# ADXL372_circuit.net
KiCad netlist of a schematic drawn in EAGLE
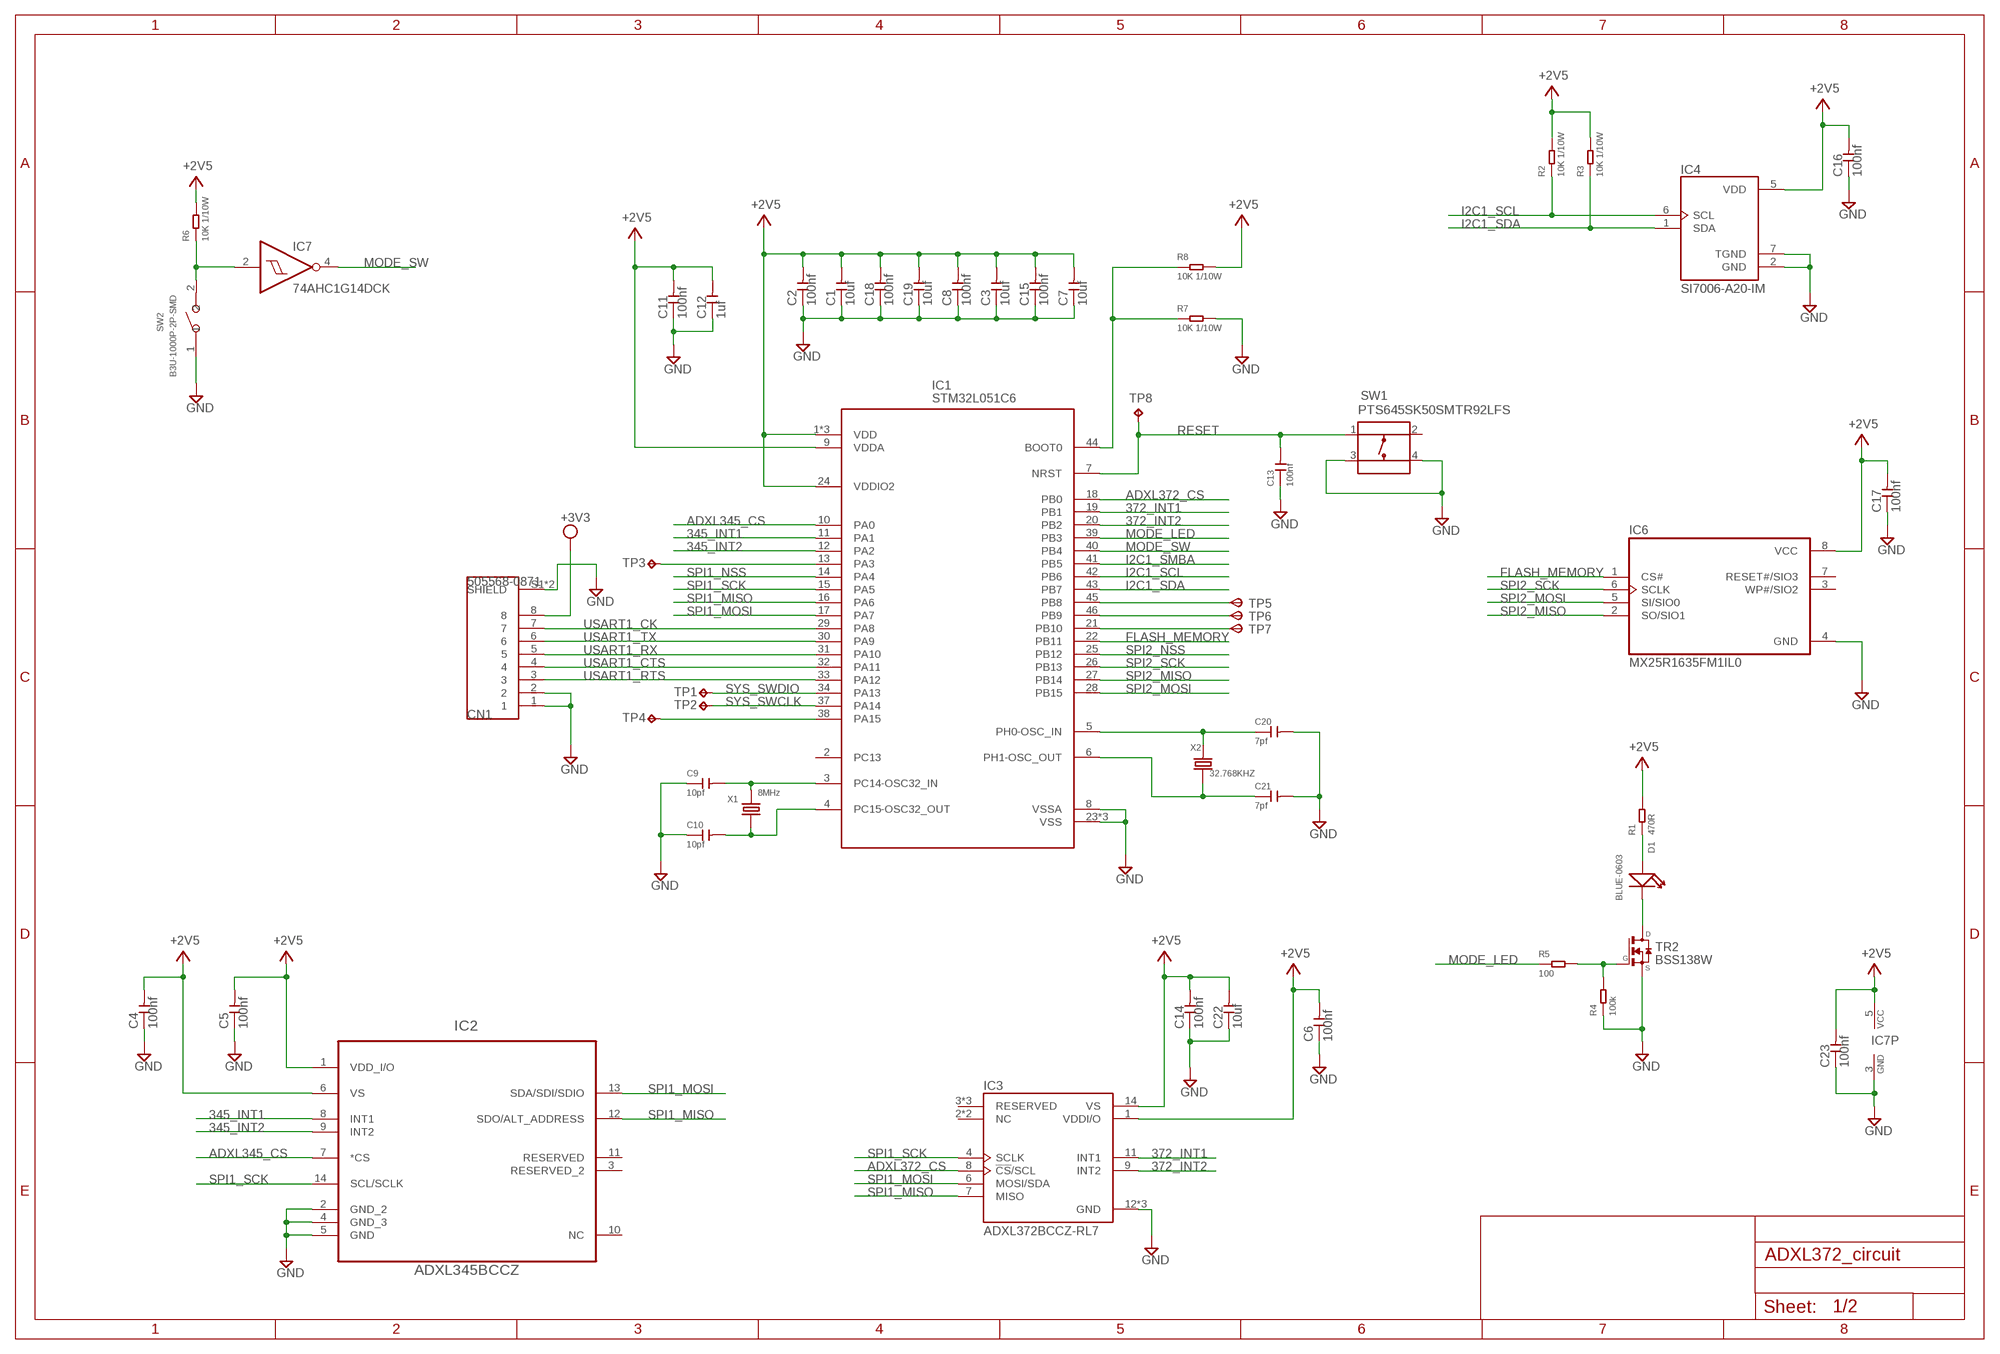
[diagram p0: schematic, sheet 1]
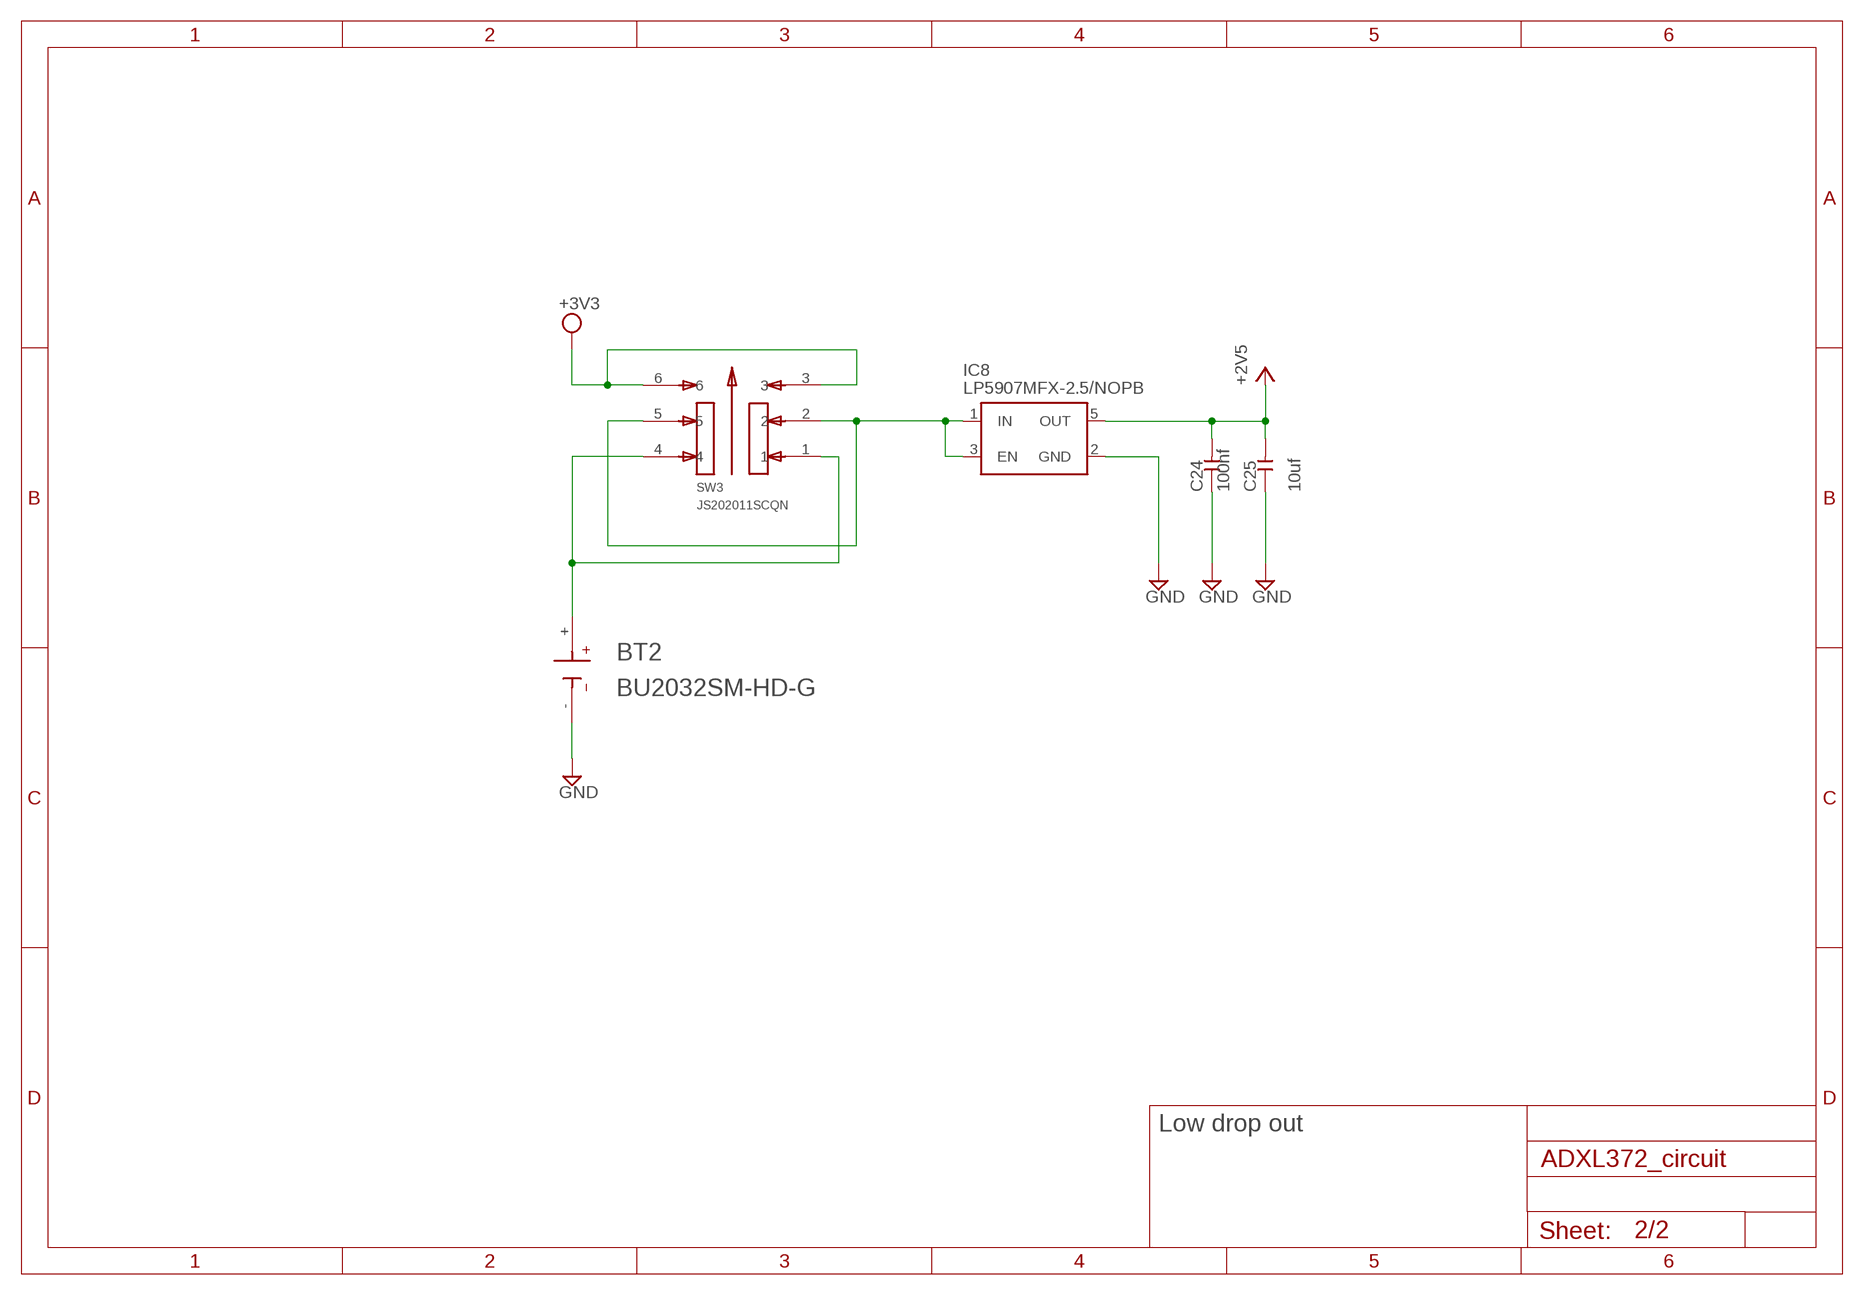
[diagram p1: schematic, sheet 2]

(export (version "E")
  (design (tool "Eeschema 10.0.6"))
  (components
    (comp (ref "BT2")
      (value "BU2032SM-HD-G")
      (footprint "eagle-import:BAT_BU2032SM-HD-G")
      (fields (field (name "DIGI-KEY_PART_NUMBER") "BU2032SM-HD-GCT-ND") (field (name "MF") "MPD _Memory"))
      (libsource (lib "eagle-import") (part "BU2032SM-HD-G"))
    )
    (comp (ref "C24")
      (value "100nf")
      (footprint "eagle-import:C0603")
      (fields (field (name "MPN") "CC0603KRX7R9BB104"))
      (libsource (lib "eagle-import") (part "CERAMIC-100NF-50V-10%-X7R(0603)"))
    )
    (comp (ref "C25")
      (value "10uf")
      (footprint "eagle-import:C0805")
      (fields (field (name "MPN") "CC0805ZKY5V6BB106"))
      (libsource (lib "eagle-import") (part "CERAMIC-10UF-10V-(-20%～+80%)-Y5V(0805)"))
    )
    (comp (ref "IC8")
      (value "LP5907MFX-2.5/NOPB")
      (footprint "eagle-import:SOT95P280X145-5N")
      (fields (field (name "DIGI-KEY_PART_NUMBER") "296-40356-1-ND") (field (name "MF") "Texas Instruments"))
      (libsource (lib "eagle-import") (part "LP5907MFX-2.5/NOPB"))
    )
    (comp (ref "SW3")
      (value "JS202011SCQN")
      (footprint "eagle-import:SW_JS202011SCQN")
      (fields (field (name "DIGI-KEY_PART_NUMBER") "401-2002-1-ND") (field (name "MF") "C&K"))
      (libsource (lib "eagle-import") (part "JS202011SCQN"))
    )
    (comp (ref "C1")
      (value "10uf")
      (footprint "eagle-import:C0805")
      (fields (field (name "MPN") "CC0805ZKY5V6BB106"))
      (libsource (lib "eagle-import") (part "CERAMIC-10UF-10V-(-20%～+80%)-Y5V(0805)"))
    )
    (comp (ref "C2")
      (value "100nf")
      (footprint "eagle-import:C0603")
      (fields (field (name "MPN") "CC0603KRX7R9BB104"))
      (libsource (lib "eagle-import") (part "CERAMIC-100NF-50V-10%-X7R(0603)"))
    )
    (comp (ref "C3")
      (value "10uf")
      (footprint "eagle-import:C0805")
      (fields (field (name "MPN") "CC0805ZKY5V6BB106"))
      (libsource (lib "eagle-import") (part "CERAMIC-10UF-10V-(-20%～+80%)-Y5V(0805)"))
    )
    (comp (ref "C4")
      (value "100nf")
      (footprint "eagle-import:C0603")
      (fields (field (name "MPN") "CC0603KRX7R9BB104"))
      (libsource (lib "eagle-import") (part "CERAMIC-100NF-50V-10%-X7R(0603)"))
    )
    (comp (ref "C5")
      (value "100nf")
      (footprint "eagle-import:C0603")
      (fields (field (name "MPN") "CC0603KRX7R9BB104"))
      (libsource (lib "eagle-import") (part "CERAMIC-100NF-50V-10%-X7R(0603)"))
    )
    (comp (ref "C6")
      (value "100nf")
      (footprint "eagle-import:C0603")
      (fields (field (name "MPN") "CC0603KRX7R9BB104"))
      (libsource (lib "eagle-import") (part "CERAMIC-100NF-50V-10%-X7R(0603)"))
    )
    (comp (ref "C7")
      (value "10uf")
      (footprint "eagle-import:C0805")
      (fields (field (name "MPN") "CC0805ZKY5V6BB106"))
      (libsource (lib "eagle-import") (part "CERAMIC-10UF-10V-(-20%～+80%)-Y5V(0805)"))
    )
    (comp (ref "C8")
      (value "100nf")
      (footprint "eagle-import:C0603")
      (fields (field (name "MPN") "CC0603KRX7R9BB104"))
      (libsource (lib "eagle-import") (part "CERAMIC-100NF-50V-10%-X7R(0603)"))
    )
    (comp (ref "C9")
      (value "10pf")
      (footprint "eagle-import:C0603")
      (fields (field (name "MPN") "CC0603JRNPO9BN100"))
      (libsource (lib "eagle-import") (part "OPL_Capacitor_8004261_CERAMIC-10PF-50V-5%-NPO(0603)"))
    )
    (comp (ref "C10")
      (value "10pf")
      (footprint "eagle-import:C0603")
      (fields (field (name "MPN") "CC0603JRNPO9BN100"))
      (libsource (lib "eagle-import") (part "OPL_Capacitor_8004261_CERAMIC-10PF-50V-5%-NPO(0603)"))
    )
    (comp (ref "C11")
      (value "100nf")
      (footprint "eagle-import:C0603")
      (fields (field (name "MPN") "CC0603KRX7R9BB104"))
      (libsource (lib "eagle-import") (part "CERAMIC-100NF-50V-10%-X7R(0603)"))
    )
    (comp (ref "C12")
      (value "1uf")
      (footprint "eagle-import:C0805")
      (fields (field (name "MPN") "CC0805KKX7R8BB105"))
      (libsource (lib "eagle-import") (part "CERAMIC-1UF-25V-10%-X7R(0805)"))
    )
    (comp (ref "C13")
      (value "100nf")
      (footprint "eagle-import:C0603")
      (fields (field (name "MPN") "CC0603KRX7R9BB104"))
      (libsource (lib "eagle-import") (part "CERAMIC-100NF-50V-10%-X7R(0603)"))
    )
    (comp (ref "C14")
      (value "100nf")
      (footprint "eagle-import:C0603")
      (fields (field (name "MPN") "CC0603KRX7R9BB104"))
      (libsource (lib "eagle-import") (part "CERAMIC-100NF-50V-10%-X7R(0603)"))
    )
    (comp (ref "C15")
      (value "100nf")
      (footprint "eagle-import:C0603")
      (fields (field (name "MPN") "CC0603KRX7R9BB104"))
      (libsource (lib "eagle-import") (part "CERAMIC-100NF-50V-10%-X7R(0603)"))
    )
    (comp (ref "C16")
      (value "100nf")
      (footprint "eagle-import:C0603")
      (fields (field (name "MPN") "CC0603KRX7R9BB104"))
      (libsource (lib "eagle-import") (part "CERAMIC-100NF-50V-10%-X7R(0603)"))
    )
    (comp (ref "C17")
      (value "100nf")
      (footprint "eagle-import:C0603")
      (fields (field (name "MPN") "CC0603KRX7R9BB104"))
      (libsource (lib "eagle-import") (part "CERAMIC-100NF-50V-10%-X7R(0603)"))
    )
    (comp (ref "C18")
      (value "100nf")
      (footprint "eagle-import:C0603")
      (fields (field (name "MPN") "CC0603KRX7R9BB104"))
      (libsource (lib "eagle-import") (part "CERAMIC-100NF-50V-10%-X7R(0603)"))
    )
    (comp (ref "C19")
      (value "10uf")
      (footprint "eagle-import:C0805")
      (fields (field (name "MPN") "CC0805ZKY5V6BB106"))
      (libsource (lib "eagle-import") (part "CERAMIC-10UF-10V-(-20%～+80%)-Y5V(0805)"))
    )
    (comp (ref "C20")
      (value "7pf")
      (footprint "eagle-import:C0603")
      (fields (field (name "MPN") "CC0603JRNPO9BN100"))
      (libsource (lib "eagle-import") (part "CERAMIC-10PF-50V-5%-NPO(0603)"))
    )
    (comp (ref "C21")
      (value "7pf")
      (footprint "eagle-import:C0603")
      (fields (field (name "MPN") "CC0603JRNPO9BN100"))
      (libsource (lib "eagle-import") (part "CERAMIC-10PF-50V-5%-NPO(0603)"))
    )
    (comp (ref "C22")
      (value "10uf")
      (footprint "eagle-import:C0805")
      (fields (field (name "MPN") "CC0805ZKY5V6BB106"))
      (libsource (lib "eagle-import") (part "CERAMIC-10UF-10V-(-20%～+80%)-Y5V(0805)"))
    )
    (comp (ref "C23")
      (value "100nf")
      (footprint "eagle-import:C0603")
      (fields (field (name "MPN") "CC0603KRX7R9BB104"))
      (libsource (lib "eagle-import") (part "CERAMIC-100NF-50V-10%-X7R(0603)"))
    )
    (comp (ref "CN1")
      (value "505568-0871")
      (footprint "eagle-import:MOLEX_505568-0871")
      (fields (field (name "MF") "Molex"))
      (libsource (lib "eagle-import") (part "505568-0871"))
    )
    (comp (ref "D1")
      (value "BLUE-0603")
      (footprint "eagle-import:LED-0603")
      (fields (field (name "MPN") "19-217-BHC-ZL1M2RY-3T"))
      (libsource (lib "eagle-import") (part "SMD-LED-CLEAR-BLUE(0603)"))
    )
    (comp (ref "IC1")
      (value "STM32L051C6")
      (footprint "eagle-import:LQFP48")
      (libsource (lib "eagle-import") (part "STM32L051C6"))
    )
    (comp (ref "IC2")
      (value "ADXL345BCCZ")
      (footprint "eagle-import:LGA14R80P3X6_300X500X100")
      (fields (field (name "DIGI-KEY_PART_NUMBER") "ADXL345BCCZ-ND") (field (name "MF") "Analog Devices"))
      (libsource (lib "eagle-import") (part "ADXL345BCCZ"))
    )
    (comp (ref "IC3")
      (value "ADXL372BCCZ-RL7")
      (footprint "eagle-import:PQFN50P322X300X114-16N")
      (fields
        (field (name "DIGI-KEY_PART_NUMBER") "ADXL372BCCZ-RL7CT-ND")
        (field (name "MF") "Analog Devices")
      )
      (libsource (lib "eagle-import") (part "ADXL372BCCZ-RL7"))
    )
    (comp (ref "IC4")
      (value "SI7006-A20-IM")
      (footprint "eagle-import:SON100P300X300X80-7N")
      (fields (field (name "MF") "Silicon Labs"))
      (libsource (lib "eagle-import") (part "SI7006-A20-IM"))
    )
    (comp (ref "IC6")
      (value "MX25R1635FM1IL0")
      (footprint "eagle-import:SOIC127P600X175-8N")
      (fields (field (name "MF") "Macronix"))
      (libsource (lib "eagle-import") (part "MX25R1635FM1IL0"))
    )
    (comp (ref "IC7")
      (value "74AHC1G14DCK")
      (footprint "eagle-import:SC70-5")
      (libsource (lib "eagle-import") (part "741G14DCKAHC"))
    )
    (comp (ref "R1")
      (value "470R")
      (footprint "eagle-import:R0603")
      (fields (field (name "MPN") "RC0603JR-07470RL"))
      (libsource (lib "eagle-import") (part "SMD-RES-470R-5%-1/10W(0603)"))
    )
    (comp (ref "R2")
      (value "10K 1/10W")
      (footprint "eagle-import:R0603")
      (fields (field (name "MPN") "RC0603JR-0710KL"))
      (libsource (lib "eagle-import") (part "SMD-RES-10K-5%-1/10W(0603)"))
    )
    (comp (ref "R3")
      (value "10K 1/10W")
      (footprint "eagle-import:R0603")
      (fields (field (name "MPN") "RC0603JR-0710KL"))
      (libsource (lib "eagle-import") (part "SMD-RES-10K-5%-1/10W(0603)"))
    )
    (comp (ref "R4")
      (value "100k")
      (footprint "eagle-import:R0603")
      (fields (field (name "MPN") "RC0603JR-07470RL"))
      (libsource (lib "eagle-import") (part "SMD-RES-470R-5%-1/10W(0603)"))
    )
    (comp (ref "R5")
      (value "100")
      (footprint "eagle-import:R0603")
      (fields (field (name "MPN") "RC0603JR-07470RL"))
      (libsource (lib "eagle-import") (part "SMD-RES-470R-5%-1/10W(0603)"))
    )
    (comp (ref "R6")
      (value "10K 1/10W")
      (footprint "eagle-import:R0603")
      (fields (field (name "MPN") "RC0603JR-0710KL"))
      (libsource (lib "eagle-import") (part "SMD-RES-10K-5%-1/10W(0603)"))
    )
    (comp (ref "R7")
      (value "10K 1/10W")
      (footprint "eagle-import:R0603")
      (fields (field (name "MPN") "RC0603JR-0710KL"))
      (libsource (lib "eagle-import") (part "SMD-RES-10K-5%-1/10W(0603)"))
    )
    (comp (ref "R8")
      (value "10K 1/10W")
      (footprint "eagle-import:R0603")
      (fields (field (name "MPN") "RC0603JR-0710KL"))
      (libsource (lib "eagle-import") (part "SMD-RES-10K-5%-1/10W(0603)"))
    )
    (comp (ref "SW1")
      (value "PTS645SK50SMTR92LFS")
      (footprint "eagle-import:SW_PTS645SK50SMTR92LFS")
      (fields (field (name "MF") "C&K"))
      (libsource (lib "eagle-import") (part "PTS645SK50SMTR92LFS"))
    )
    (comp (ref "SW2")
      (value "B3U-1000P-2P-SMD")
      (footprint "eagle-import:SW2-2.6-3.0X2.5X1.2+0.4MM")
      (libsource (lib "eagle-import") (part "SMD-BUTTON(2P-3.0X2.5X1.2+0.4MM)-B3U-1000P-2P-SMD"))
    )
    (comp (ref "TP1")
      (value "TPB1,27")
      (footprint "eagle-import:B1,27")
      (libsource (lib "eagle-import") (part "TPB1,27"))
    )
    (comp (ref "TP2")
      (value "TPB1,27")
      (footprint "eagle-import:B1,27")
      (libsource (lib "eagle-import") (part "TPB1,27"))
    )
    (comp (ref "TP3")
      (value "TPB1,27")
      (footprint "eagle-import:B1,27")
      (libsource (lib "eagle-import") (part "TPB1,27"))
    )
    (comp (ref "TP4")
      (value "TPB1,27")
      (footprint "eagle-import:B1,27")
      (libsource (lib "eagle-import") (part "TPB1,27"))
    )
    (comp (ref "TP5")
      (value "TPSB1,27")
      (footprint "eagle-import:B1,27")
      (libsource (lib "eagle-import") (part "TPSB1,27"))
    )
    (comp (ref "TP6")
      (value "TPSB1,27")
      (footprint "eagle-import:B1,27")
      (libsource (lib "eagle-import") (part "TPSB1,27"))
    )
    (comp (ref "TP7")
      (value "TPSB1,27")
      (footprint "eagle-import:B1,27")
      (libsource (lib "eagle-import") (part "TPSB1,27"))
    )
    (comp (ref "TP8")
      (value "TPB1,27")
      (footprint "eagle-import:B1,27")
      (libsource (lib "eagle-import") (part "TPB1,27"))
    )
    (comp (ref "TR2")
      (value "BSS138W")
      (footprint "eagle-import:SOT323-R")
      (fields (field (name "DIGI-KEY_PART_NUMBER") "BSS138WCT-ND") (field (name "MF") "ON Semiconductor"))
      (libsource (lib "eagle-import") (part "BSS138W"))
    )
    (comp (ref "X1")
      (value "8MHz")
      (footprint "eagle-import:X2-SMD-5.0X3.2X1.3MM")
      (fields (field (name "MPN") "X053201602002"))
      (libsource (lib "eagle-import") (part "SMD-CRYSTAL-16MHZ-8PF-20PPM-40R(2P-5.0X3.2MM)"))
    )
    (comp (ref "X2")
      (value "32.768KHZ")
      (footprint "eagle-import:X2-SMD-L2.0X1.2X0.55MM")
      (fields (field (name "MPN") "FC-12M"))
      (libsource (lib "eagle-import") (part "SMD-CRYSTAL-32.768KHZ-12.5PF-20PPM-90K(2P-L2.0X1.2MM)"))
    )
  )
  (nets
    (net (code "1") (name "+2V5") (class "Default")
      (node (ref "C1") (pin "2") (pinfunction "2_2") (pintype "passive"))
      (node (ref "C11") (pin "2") (pinfunction "2_2") (pintype "passive"))
      (node (ref "C12") (pin "2") (pinfunction "2_2") (pintype "passive"))
      (node (ref "C14") (pin "2") (pinfunction "2_2") (pintype "passive"))
      (node (ref "C15") (pin "2") (pinfunction "2_2") (pintype "passive"))
      (node (ref "C16") (pin "2") (pinfunction "2_2") (pintype "passive"))
      (node (ref "C17") (pin "2") (pinfunction "2_2") (pintype "passive"))
      (node (ref "C18") (pin "2") (pinfunction "2_2") (pintype "passive"))
      (node (ref "C19") (pin "2") (pinfunction "2_2") (pintype "passive"))
      (node (ref "C2") (pin "2") (pinfunction "2_2") (pintype "passive"))
      (node (ref "C22") (pin "2") (pinfunction "2_2") (pintype "passive"))
      (node (ref "C23") (pin "2") (pinfunction "2_2") (pintype "passive"))
      (node (ref "C24") (pin "2") (pinfunction "2_2") (pintype "passive"))
      (node (ref "C25") (pin "2") (pinfunction "2_2") (pintype "passive"))
      (node (ref "C3") (pin "2") (pinfunction "2_2") (pintype "passive"))
      (node (ref "C4") (pin "2") (pinfunction "2_2") (pintype "passive"))
      (node (ref "C5") (pin "2") (pinfunction "2_2") (pintype "passive"))
      (node (ref "C6") (pin "2") (pinfunction "2_2") (pintype "passive"))
      (node (ref "C7") (pin "2") (pinfunction "2_2") (pintype "passive"))
      (node (ref "C8") (pin "2") (pinfunction "2_2") (pintype "passive"))
      (node (ref "IC1") (pin "1") (pinfunction "VDD_1") (pintype "power_in"))
      (node (ref "IC1") (pin "24") (pinfunction "VDDIO2_24") (pintype "bidirectional"))
      (node (ref "IC1") (pin "36") (pinfunction "VDD_36") (pintype "power_in"))
      (node (ref "IC1") (pin "48") (pinfunction "VDD_48") (pintype "power_in"))
      (node (ref "IC1") (pin "9") (pinfunction "VDDA_9") (pintype "power_in"))
      (node (ref "IC2") (pin "1") (pinfunction "VDD_I/O_1") (pintype "passive"))
      (node (ref "IC2") (pin "6") (pinfunction "VS_6") (pintype "passive"))
      (node (ref "IC3") (pin "1") (pinfunction "VDDI/O_1") (pintype "power_in"))
      (node (ref "IC3") (pin "14") (pinfunction "VS_14") (pintype "power_in"))
      (node (ref "IC4") (pin "5") (pinfunction "VDD_5") (pintype "power_in"))
      (node (ref "IC6") (pin "8") (pinfunction "VCC_8") (pintype "power_in"))
      (node (ref "IC7") (pin "5") (pinfunction "VCC_5") (pintype "power_in"))
      (node (ref "IC8") (pin "5") (pinfunction "OUT_5") (pintype "output"))
      (node (ref "R1") (pin "2") (pinfunction "2_2") (pintype "passive"))
      (node (ref "R2") (pin "2") (pinfunction "2_2") (pintype "passive"))
      (node (ref "R3") (pin "2") (pinfunction "2_2") (pintype "passive"))
      (node (ref "R6") (pin "2") (pinfunction "2_2") (pintype "passive"))
      (node (ref "R8") (pin "2") (pinfunction "2_2") (pintype "passive"))
    )
    (net (code "2") (name "+3V3") (class "Default")
      (node (ref "CN1") (pin "8") (pinfunction "8_8") (pintype "passive"))
      (node (ref "SW3") (pin "3") (pinfunction "3_3") (pintype "passive"))
      (node (ref "SW3") (pin "6") (pinfunction "6_6") (pintype "passive"))
    )
    (net (code "3") (name "345_INT1") (class "Default")
      (node (ref "IC1") (pin "11") (pinfunction "PA1_11") (pintype "bidirectional"))
      (node (ref "IC2") (pin "8") (pinfunction "INT1_8") (pintype "passive"))
    )
    (net (code "4") (name "345_INT2") (class "Default")
      (node (ref "IC1") (pin "12") (pinfunction "PA2_12") (pintype "bidirectional"))
      (node (ref "IC2") (pin "9") (pinfunction "INT2_9") (pintype "passive"))
    )
    (net (code "5") (name "372_INT1") (class "Default")
      (node (ref "IC1") (pin "19") (pinfunction "PB1_19") (pintype "bidirectional"))
      (node (ref "IC3") (pin "11") (pinfunction "INT1_11") (pintype "output"))
    )
    (net (code "6") (name "372_INT2") (class "Default")
      (node (ref "IC1") (pin "20") (pinfunction "PB2_20") (pintype "bidirectional"))
      (node (ref "IC3") (pin "9") (pinfunction "INT2_9") (pintype "output"))
    )
    (net (code "7") (name "ADXL345_CS") (class "Default")
      (node (ref "IC1") (pin "10") (pinfunction "PA0_10") (pintype "bidirectional"))
      (node (ref "IC2") (pin "7") (pinfunction "*CS_7") (pintype "passive"))
    )
    (net (code "8") (name "ADXL372_CS") (class "Default")
      (node (ref "IC1") (pin "18") (pinfunction "PB0_18") (pintype "bidirectional"))
      (node (ref "IC3") (pin "8") (pinfunction "~{CS}/SCL_8") (pintype "input"))
    )
    (net (code "9") (name "FLASH_MEMORY") (class "Default")
      (node (ref "IC1") (pin "22") (pinfunction "PB11_22") (pintype "bidirectional"))
      (node (ref "IC6") (pin "1") (pinfunction "CS#_1") (pintype "input"))
    )
    (net (code "10") (name "GND") (class "Default")
      (node (ref "BT2") (pin "-") (pinfunction "-_-") (pintype "passive"))
      (node (ref "C1") (pin "1") (pinfunction "1_1") (pintype "passive"))
      (node (ref "C10") (pin "1") (pinfunction "1_1") (pintype "passive"))
      (node (ref "C11") (pin "1") (pinfunction "1_1") (pintype "passive"))
      (node (ref "C12") (pin "1") (pinfunction "1_1") (pintype "passive"))
      (node (ref "C13") (pin "1") (pinfunction "1_1") (pintype "passive"))
      (node (ref "C14") (pin "1") (pinfunction "1_1") (pintype "passive"))
      (node (ref "C15") (pin "1") (pinfunction "1_1") (pintype "passive"))
      (node (ref "C16") (pin "1") (pinfunction "1_1") (pintype "passive"))
      (node (ref "C17") (pin "1") (pinfunction "1_1") (pintype "passive"))
      (node (ref "C18") (pin "1") (pinfunction "1_1") (pintype "passive"))
      (node (ref "C19") (pin "1") (pinfunction "1_1") (pintype "passive"))
      (node (ref "C2") (pin "1") (pinfunction "1_1") (pintype "passive"))
      (node (ref "C20") (pin "2") (pinfunction "2_2") (pintype "passive"))
      (node (ref "C21") (pin "2") (pinfunction "2_2") (pintype "passive"))
      (node (ref "C22") (pin "1") (pinfunction "1_1") (pintype "passive"))
      (node (ref "C23") (pin "1") (pinfunction "1_1") (pintype "passive"))
      (node (ref "C24") (pin "1") (pinfunction "1_1") (pintype "passive"))
      (node (ref "C25") (pin "1") (pinfunction "1_1") (pintype "passive"))
      (node (ref "C3") (pin "1") (pinfunction "1_1") (pintype "passive"))
      (node (ref "C4") (pin "1") (pinfunction "1_1") (pintype "passive"))
      (node (ref "C5") (pin "1") (pinfunction "1_1") (pintype "passive"))
      (node (ref "C6") (pin "1") (pinfunction "1_1") (pintype "passive"))
      (node (ref "C7") (pin "1") (pinfunction "1_1") (pintype "passive"))
      (node (ref "C8") (pin "1") (pinfunction "1_1") (pintype "passive"))
      (node (ref "C9") (pin "1") (pinfunction "1_1") (pintype "passive"))
      (node (ref "CN1") (pin "1") (pinfunction "1_1") (pintype "passive"))
      (node (ref "CN1") (pin "2") (pinfunction "2_2") (pintype "passive"))
      (node (ref "CN1") (pin "S1") (pinfunction "SHIELD_S1") (pintype "passive"))
      (node (ref "CN1") (pin "S2") (pinfunction "SHIELD_S2") (pintype "passive"))
      (node (ref "IC1") (pin "23") (pinfunction "VSS_23") (pintype "bidirectional"))
      (node (ref "IC1") (pin "35") (pinfunction "VSS_35") (pintype "bidirectional"))
      (node (ref "IC1") (pin "47") (pinfunction "VSS_47") (pintype "bidirectional"))
      (node (ref "IC1") (pin "8") (pinfunction "VSSA_8") (pintype "bidirectional"))
      (node (ref "IC2") (pin "2") (pinfunction "GND_2_2") (pintype "passive"))
      (node (ref "IC2") (pin "4") (pinfunction "GND_3_4") (pintype "passive"))
      (node (ref "IC2") (pin "5") (pinfunction "GND_5") (pintype "passive"))
      (node (ref "IC3") (pin "12") (pinfunction "GND_12") (pintype "power_in"))
      (node (ref "IC3") (pin "13") (pinfunction "GND_13") (pintype "power_in"))
      (node (ref "IC3") (pin "16") (pinfunction "GND_16") (pintype "power_in"))
      (node (ref "IC4") (pin "2") (pinfunction "GND_2") (pintype "power_in"))
      (node (ref "IC4") (pin "7") (pinfunction "TGND_7") (pintype "power_in"))
      (node (ref "IC6") (pin "4") (pinfunction "GND_4") (pintype "power_in"))
      (node (ref "IC7") (pin "3") (pinfunction "GND_3") (pintype "power_in"))
      (node (ref "IC8") (pin "2") (pinfunction "GND_2") (pintype "power_in"))
      (node (ref "R4") (pin "1") (pinfunction "1_1") (pintype "passive"))
      (node (ref "R7") (pin "2") (pinfunction "2_2") (pintype "passive"))
      (node (ref "SW1") (pin "3") (pinfunction "3_3") (pintype "passive"))
      (node (ref "SW1") (pin "4") (pinfunction "4_4") (pintype "passive"))
      (node (ref "SW2") (pin "1") (pinfunction "1_1") (pintype "bidirectional"))
      (node (ref "TR2") (pin "2") (pinfunction "S_2") (pintype "passive"))
    )
    (net (code "11") (name "I2C1_SCL") (class "Default")
      (node (ref "IC1") (pin "42") (pinfunction "PB6_42") (pintype "bidirectional"))
      (node (ref "IC4") (pin "6") (pinfunction "SCL_6") (pintype "bidirectional"))
      (node (ref "R2") (pin "1") (pinfunction "1_1") (pintype "passive"))
    )
    (net (code "12") (name "I2C1_SDA") (class "Default")
      (node (ref "IC1") (pin "43") (pinfunction "PB7_43") (pintype "bidirectional"))
      (node (ref "IC4") (pin "1") (pinfunction "SDA_1") (pintype "bidirectional"))
      (node (ref "R3") (pin "1") (pinfunction "1_1") (pintype "passive"))
    )
    (net (code "13") (name "I2C1_SMBA") (class "Default")
      (node (ref "IC1") (pin "41") (pinfunction "PB5_41") (pintype "bidirectional"))
    )
    (net (code "14") (name "MODE_LED") (class "Default")
      (node (ref "IC1") (pin "39") (pinfunction "PB3_39") (pintype "bidirectional"))
      (node (ref "R5") (pin "1") (pinfunction "1_1") (pintype "passive"))
    )
    (net (code "15") (name "MODE_SW") (class "Default")
      (node (ref "IC1") (pin "40") (pinfunction "PB4_40") (pintype "bidirectional"))
      (node (ref "IC7") (pin "4") (pinfunction "O_4") (pintype "output"))
    )
    (net (code "16") (name "Net-(BT2-Pad+)") (class "Default")
      (node (ref "BT2") (pin "+") (pinfunction "+_+") (pintype "passive"))
      (node (ref "SW3") (pin "1") (pinfunction "1_1") (pintype "passive"))
      (node (ref "SW3") (pin "4") (pinfunction "4_4") (pintype "passive"))
    )
    (net (code "17") (name "Net-(D1-Pad+)") (class "Default")
      (node (ref "D1") (pin "+") (pinfunction "+_+") (pintype "passive"))
      (node (ref "R1") (pin "1") (pinfunction "1_1") (pintype "passive"))
    )
    (net (code "18") (name "Net-(IC1-BOOT0)") (class "Default")
      (node (ref "IC1") (pin "44") (pinfunction "BOOT0_44") (pintype "bidirectional"))
      (node (ref "R7") (pin "1") (pinfunction "1_1") (pintype "passive"))
      (node (ref "R8") (pin "1") (pinfunction "1_1") (pintype "passive"))
    )
    (net (code "19") (name "Net-(IC1-PA3)") (class "Default")
      (node (ref "IC1") (pin "13") (pinfunction "PA3_13") (pintype "bidirectional"))
      (node (ref "TP3") (pin "TP") (pinfunction "TP_TP") (pintype "input"))
    )
    (net (code "20") (name "Net-(IC1-PA15)") (class "Default")
      (node (ref "IC1") (pin "38") (pinfunction "PA15_38") (pintype "bidirectional"))
      (node (ref "TP4") (pin "TP") (pinfunction "TP_TP") (pintype "input"))
    )
    (net (code "21") (name "Net-(IC1-PB8)") (class "Default")
      (node (ref "IC1") (pin "45") (pinfunction "PB8_45") (pintype "bidirectional"))
      (node (ref "TP5") (pin "TP") (pinfunction "PP_TP") (pintype "input"))
    )
    (net (code "22") (name "Net-(IC1-PB9)") (class "Default")
      (node (ref "IC1") (pin "46") (pinfunction "PB9_46") (pintype "bidirectional"))
      (node (ref "TP6") (pin "TP") (pinfunction "PP_TP") (pintype "input"))
    )
    (net (code "23") (name "Net-(IC1-PB10)") (class "Default")
      (node (ref "IC1") (pin "21") (pinfunction "PB10_21") (pintype "bidirectional"))
      (node (ref "TP7") (pin "TP") (pinfunction "PP_TP") (pintype "input"))
    )
    (net (code "24") (name "Net-(IC1-PC14-OSC32_IN)") (class "Default")
      (node (ref "C9") (pin "2") (pinfunction "2_2") (pintype "passive"))
      (node (ref "IC1") (pin "3") (pinfunction "PC14-OSC32_IN_3") (pintype "bidirectional"))
      (node (ref "X1") (pin "2") (pinfunction "2_2") (pintype "passive"))
    )
    (net (code "25") (name "Net-(IC1-PC15-OSC32_OUT)") (class "Default")
      (node (ref "C10") (pin "2") (pinfunction "2_2") (pintype "passive"))
      (node (ref "IC1") (pin "4") (pinfunction "PC15-OSC32_OUT_4") (pintype "bidirectional"))
      (node (ref "X1") (pin "1") (pinfunction "1_1") (pintype "passive"))
    )
    (net (code "26") (name "Net-(IC1-PH0-OSC_IN)") (class "Default")
      (node (ref "C20") (pin "1") (pinfunction "1_1") (pintype "passive"))
      (node (ref "IC1") (pin "5") (pinfunction "PH0-OSC_IN_5") (pintype "bidirectional"))
      (node (ref "X2") (pin "2") (pinfunction "2_2") (pintype "passive"))
    )
    (net (code "27") (name "Net-(IC1-PH1-OSC_OUT)") (class "Default")
      (node (ref "C21") (pin "1") (pinfunction "1_1") (pintype "passive"))
      (node (ref "IC1") (pin "6") (pinfunction "PH1-OSC_OUT_6") (pintype "bidirectional"))
      (node (ref "X2") (pin "1") (pinfunction "1_1") (pintype "passive"))
    )
    (net (code "28") (name "Net-(IC7A-I)") (class "Default")
      (node (ref "IC7") (pin "2") (pinfunction "I_2") (pintype "input"))
      (node (ref "R6") (pin "1") (pinfunction "1_1") (pintype "passive"))
      (node (ref "SW2") (pin "2") (pinfunction "2_2") (pintype "bidirectional"))
    )
    (net (code "29") (name "Net-(IC8-EN)") (class "Default")
      (node (ref "IC8") (pin "1") (pinfunction "IN_1") (pintype "input"))
      (node (ref "IC8") (pin "3") (pinfunction "EN_3") (pintype "input"))
      (node (ref "SW3") (pin "2") (pinfunction "2_2") (pintype "passive"))
      (node (ref "SW3") (pin "5") (pinfunction "5_5") (pintype "passive"))
    )
    (net (code "30") (name "Net-(TR2-D)") (class "Default")
      (node (ref "D1") (pin "-") (pinfunction "-_-") (pintype "passive"))
      (node (ref "TR2") (pin "3") (pinfunction "D_3") (pintype "passive"))
    )
    (net (code "31") (name "Net-(TR2-G)") (class "Default")
      (node (ref "R4") (pin "2") (pinfunction "2_2") (pintype "passive"))
      (node (ref "R5") (pin "2") (pinfunction "2_2") (pintype "passive"))
      (node (ref "TR2") (pin "1") (pinfunction "G_1") (pintype "passive"))
    )
    (net (code "32") (name "RESET") (class "Default")
      (node (ref "C13") (pin "2") (pinfunction "2_2") (pintype "passive"))
      (node (ref "IC1") (pin "7") (pinfunction "NRST_7") (pintype "bidirectional"))
      (node (ref "SW1") (pin "1") (pinfunction "1_1") (pintype "passive"))
      (node (ref "TP8") (pin "TP") (pinfunction "TP_TP") (pintype "input"))
    )
    (net (code "33") (name "SPI1_MISO") (class "Default")
      (node (ref "IC1") (pin "16") (pinfunction "PA6_16") (pintype "bidirectional"))
      (node (ref "IC2") (pin "12") (pinfunction "SDO/ALT_ADDRESS_12") (pintype "passive"))
      (node (ref "IC3") (pin "7") (pinfunction "MISO_7") (pintype "output"))
    )
    (net (code "34") (name "SPI1_MOSI") (class "Default")
      (node (ref "IC1") (pin "17") (pinfunction "PA7_17") (pintype "bidirectional"))
      (node (ref "IC2") (pin "13") (pinfunction "SDA/SDI/SDIO_13") (pintype "passive"))
      (node (ref "IC3") (pin "6") (pinfunction "MOSI/SDA_6") (pintype "bidirectional"))
    )
    (net (code "35") (name "SPI1_NSS") (class "Default")
      (node (ref "IC1") (pin "14") (pinfunction "PA4_14") (pintype "bidirectional"))
    )
    (net (code "36") (name "SPI1_SCK") (class "Default")
      (node (ref "IC1") (pin "15") (pinfunction "PA5_15") (pintype "bidirectional"))
      (node (ref "IC2") (pin "14") (pinfunction "SCL/SCLK_14") (pintype "passive"))
      (node (ref "IC3") (pin "4") (pinfunction "SCLK_4") (pintype "input"))
    )
    (net (code "37") (name "SPI2_MISO") (class "Default")
      (node (ref "IC1") (pin "27") (pinfunction "PB14_27") (pintype "bidirectional"))
      (node (ref "IC6") (pin "2") (pinfunction "SO/SIO1_2") (pintype "bidirectional"))
    )
    (net (code "38") (name "SPI2_MOSI") (class "Default")
      (node (ref "IC1") (pin "28") (pinfunction "PB15_28") (pintype "bidirectional"))
      (node (ref "IC6") (pin "5") (pinfunction "SI/SIO0_5") (pintype "bidirectional"))
    )
    (net (code "39") (name "SPI2_NSS") (class "Default")
      (node (ref "IC1") (pin "25") (pinfunction "PB12_25") (pintype "bidirectional"))
    )
    (net (code "40") (name "SPI2_SCK") (class "Default")
      (node (ref "IC1") (pin "26") (pinfunction "PB13_26") (pintype "bidirectional"))
      (node (ref "IC6") (pin "6") (pinfunction "SCLK_6") (pintype "input"))
    )
    (net (code "41") (name "SYS_SWCLK") (class "Default")
      (node (ref "IC1") (pin "37") (pinfunction "PA14_37") (pintype "bidirectional"))
      (node (ref "TP2") (pin "TP") (pinfunction "TP_TP") (pintype "input"))
    )
    (net (code "42") (name "SYS_SWDIO") (class "Default")
      (node (ref "IC1") (pin "34") (pinfunction "PA13_34") (pintype "bidirectional"))
      (node (ref "TP1") (pin "TP") (pinfunction "TP_TP") (pintype "input"))
    )
    (net (code "43") (name "USART1_CK") (class "Default")
      (node (ref "CN1") (pin "7") (pinfunction "7_7") (pintype "passive"))
      (node (ref "IC1") (pin "29") (pinfunction "PA8_29") (pintype "bidirectional"))
    )
    (net (code "44") (name "USART1_CTS") (class "Default")
      (node (ref "CN1") (pin "4") (pinfunction "4_4") (pintype "passive"))
      (node (ref "IC1") (pin "32") (pinfunction "PA11_32") (pintype "bidirectional"))
    )
    (net (code "45") (name "USART1_RTS") (class "Default")
      (node (ref "CN1") (pin "3") (pinfunction "3_3") (pintype "passive"))
      (node (ref "IC1") (pin "33") (pinfunction "PA12_33") (pintype "bidirectional"))
    )
    (net (code "46") (name "USART1_RX") (class "Default")
      (node (ref "CN1") (pin "5") (pinfunction "5_5") (pintype "passive"))
      (node (ref "IC1") (pin "31") (pinfunction "PA10_31") (pintype "bidirectional"))
    )
    (net (code "47") (name "USART1_TX") (class "Default")
      (node (ref "CN1") (pin "6") (pinfunction "6_6") (pintype "passive"))
      (node (ref "IC1") (pin "30") (pinfunction "PA9_30") (pintype "bidirectional"))
    )
    (net (code "48") (name "unconnected-(IC1-PC13-Pad2)") (class "Default")
      (node (ref "IC1") (pin "2") (pinfunction "PC13_2") (pintype "bidirectional"))
    )
    (net (code "49") (name "unconnected-(IC2-NC-Pad10)") (class "Default")
      (node (ref "IC2") (pin "10") (pinfunction "NC_10") (pintype "passive"))
    )
    (net (code "50") (name "unconnected-(IC2-RESERVED-Pad11)") (class "Default")
      (node (ref "IC2") (pin "11") (pinfunction "RESERVED_11") (pintype "passive"))
    )
    (net (code "51") (name "unconnected-(IC2-RESERVED_2-Pad3)") (class "Default")
      (node (ref "IC2") (pin "3") (pinfunction "RESERVED_2_3") (pintype "passive"))
    )
    (net (code "52") (name "unconnected-(IC3-NC-Pad2)") (class "Default")
      (node (ref "IC3") (pin "2") (pinfunction "NC_2") (pintype "no_connect"))
    )
    (net (code "53") (name "unconnected-(IC3-NC-Pad15)") (class "Default")
      (node (ref "IC3") (pin "15") (pinfunction "NC_15") (pintype "no_connect"))
    )
    (net (code "54") (name "unconnected-(IC3-RESERVED-Pad3)") (class "Default")
      (node (ref "IC3") (pin "3") (pinfunction "RESERVED_3") (pintype "no_connect"))
    )
    (net (code "55") (name "unconnected-(IC3-RESERVED-Pad5)") (class "Default")
      (node (ref "IC3") (pin "5") (pinfunction "RESERVED_5") (pintype "no_connect"))
    )
    (net (code "56") (name "unconnected-(IC3-RESERVED-Pad10)") (class "Default")
      (node (ref "IC3") (pin "10") (pinfunction "RESERVED_10") (pintype "no_connect"))
    )
    (net (code "57") (name "unconnected-(IC6-RESET#{slash}SIO3-Pad7)") (class "Default")
      (node (ref "IC6") (pin "7") (pinfunction "RESET#/SIO3_7") (pintype "bidirectional"))
    )
    (net (code "58") (name "unconnected-(IC6-WP#{slash}SIO2-Pad3)") (class "Default")
      (node (ref "IC6") (pin "3") (pinfunction "WP#/SIO2_3") (pintype "bidirectional"))
    )
    (net (code "59") (name "unconnected-(SW1-Pad2)") (class "Default")
      (node (ref "SW1") (pin "2") (pinfunction "2_2") (pintype "passive"))
    )
  )
)
